# WS2812B_Bar.net
KiCad netlist of a schematic drawn in Altium Designer
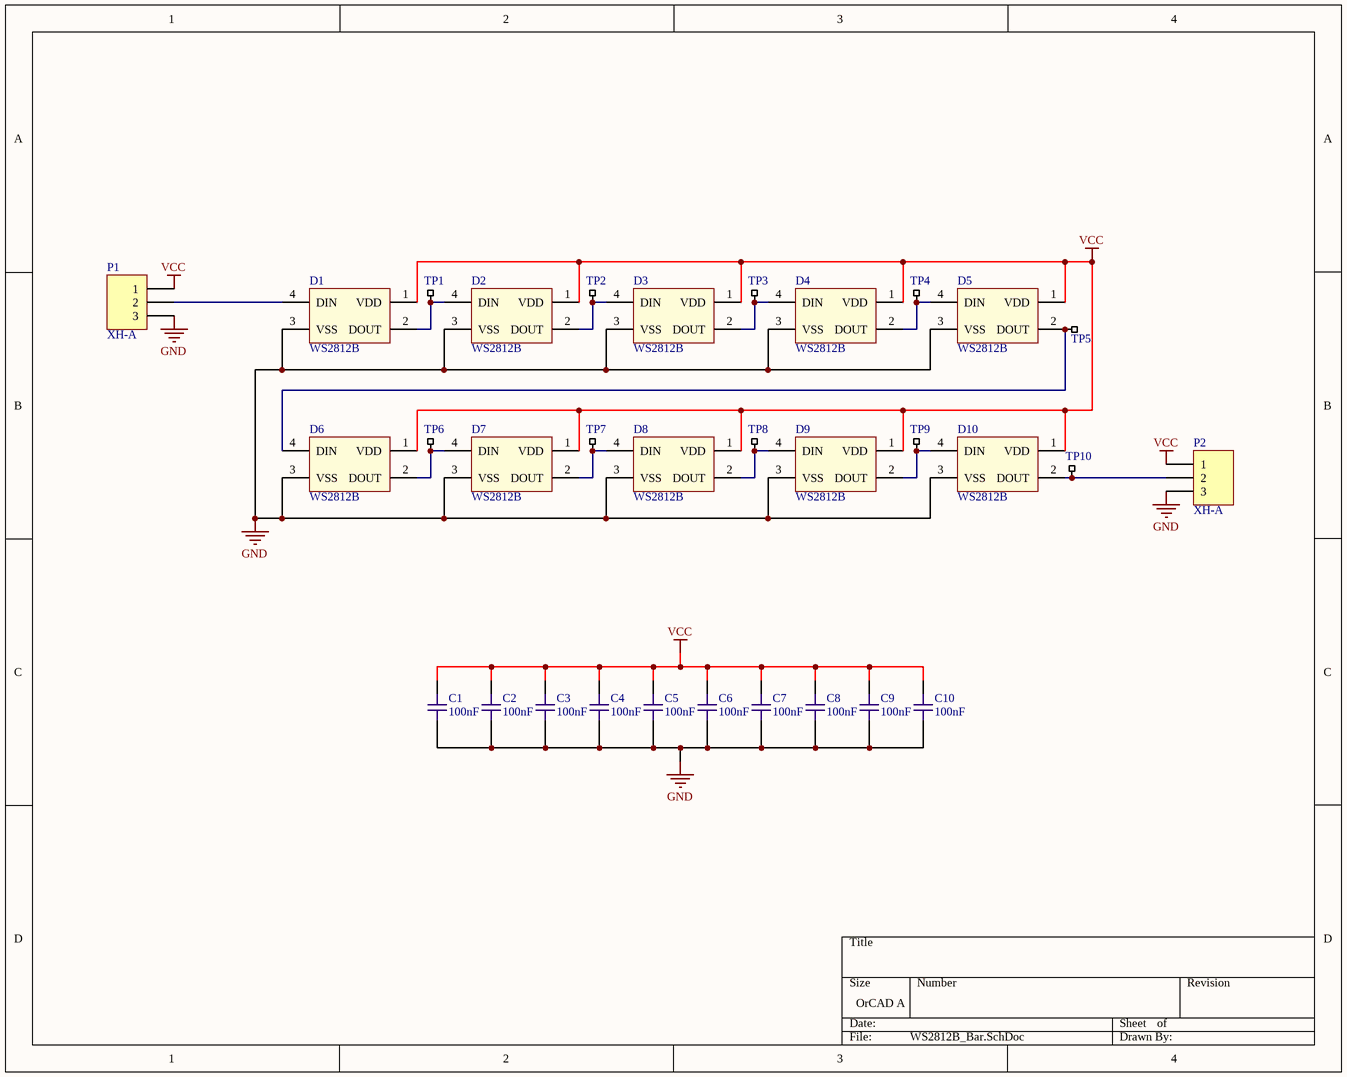
[diagram p0: WS2812B_Bar.SchDoc]

(export (version "E")
  (design (tool "Eeschema 10.0.6"))
  (components
    (comp (ref "C1")
      (value "100nF")
      (footprint "C0603-IPC")
      (description "Chip Capacitor, 0603, 100nF, 25V, X7R")
      (fields (field (name "Comment") "C0603 100nF 25V X7R"))
      (libsource (lib "Capacitors") (part "C0603 100nF 25V X7R"))
    )
    (comp (ref "C2")
      (value "100nF")
      (footprint "C0603-IPC")
      (description "Chip Capacitor, 0603, 100nF, 25V, X7R")
      (fields (field (name "Comment") "C0603 100nF 25V X7R"))
      (libsource (lib "Capacitors") (part "C0603 100nF 25V X7R"))
    )
    (comp (ref "C3")
      (value "100nF")
      (footprint "C0603-IPC")
      (description "Chip Capacitor, 0603, 100nF, 25V, X7R")
      (fields (field (name "Comment") "C0603 100nF 25V X7R"))
      (libsource (lib "Capacitors") (part "C0603 100nF 25V X7R"))
    )
    (comp (ref "C4")
      (value "100nF")
      (footprint "C0603-IPC")
      (description "Chip Capacitor, 0603, 100nF, 25V, X7R")
      (fields (field (name "Comment") "C0603 100nF 25V X7R"))
      (libsource (lib "Capacitors") (part "C0603 100nF 25V X7R"))
    )
    (comp (ref "C5")
      (value "100nF")
      (footprint "C0603-IPC")
      (description "Chip Capacitor, 0603, 100nF, 25V, X7R")
      (fields (field (name "Comment") "C0603 100nF 25V X7R"))
      (libsource (lib "Capacitors") (part "C0603 100nF 25V X7R"))
    )
    (comp (ref "C6")
      (value "100nF")
      (footprint "C0603-IPC")
      (description "Chip Capacitor, 0603, 100nF, 25V, X7R")
      (fields (field (name "Comment") "C0603 100nF 25V X7R"))
      (libsource (lib "Capacitors") (part "C0603 100nF 25V X7R"))
    )
    (comp (ref "C7")
      (value "100nF")
      (footprint "C0603-IPC")
      (description "Chip Capacitor, 0603, 100nF, 25V, X7R")
      (fields (field (name "Comment") "C0603 100nF 25V X7R"))
      (libsource (lib "Capacitors") (part "C0603 100nF 25V X7R"))
    )
    (comp (ref "C8")
      (value "100nF")
      (footprint "C0603-IPC")
      (description "Chip Capacitor, 0603, 100nF, 25V, X7R")
      (fields (field (name "Comment") "C0603 100nF 25V X7R"))
      (libsource (lib "Capacitors") (part "C0603 100nF 25V X7R"))
    )
    (comp (ref "C9")
      (value "100nF")
      (footprint "C0603-IPC")
      (description "Chip Capacitor, 0603, 100nF, 25V, X7R")
      (fields (field (name "Comment") "C0603 100nF 25V X7R"))
      (libsource (lib "Capacitors") (part "C0603 100nF 25V X7R"))
    )
    (comp (ref "C10")
      (value "100nF")
      (footprint "C0603-IPC")
      (description "Chip Capacitor, 0603, 100nF, 25V, X7R")
      (fields (field (name "Comment") "C0603 100nF 25V X7R"))
      (libsource (lib "Capacitors") (part "C0603 100nF 25V X7R"))
    )
    (comp (ref "D1")
      (value "WS2812B")
      (footprint "WS2812B")
      (description "Addressable Lighting - Discrete Serial Red, Green, Blue (RGB) 5.00mm L x 5.00mm WS2812B")
      (libsource (lib "Diodes") (part "WS2812B"))
    )
    (comp (ref "D2")
      (value "WS2812B")
      (footprint "WS2812B")
      (description "Addressable Lighting - Discrete Serial Red, Green, Blue (RGB) 5.00mm L x 5.00mm WS2812B")
      (libsource (lib "Diodes") (part "WS2812B"))
    )
    (comp (ref "D3")
      (value "WS2812B")
      (footprint "WS2812B")
      (description "Addressable Lighting - Discrete Serial Red, Green, Blue (RGB) 5.00mm L x 5.00mm WS2812B")
      (libsource (lib "Diodes") (part "WS2812B"))
    )
    (comp (ref "D4")
      (value "WS2812B")
      (footprint "WS2812B")
      (description "Addressable Lighting - Discrete Serial Red, Green, Blue (RGB) 5.00mm L x 5.00mm WS2812B")
      (libsource (lib "Diodes") (part "WS2812B"))
    )
    (comp (ref "D5")
      (value "WS2812B")
      (footprint "WS2812B")
      (description "Addressable Lighting - Discrete Serial Red, Green, Blue (RGB) 5.00mm L x 5.00mm WS2812B")
      (libsource (lib "Diodes") (part "WS2812B"))
    )
    (comp (ref "D6")
      (value "WS2812B")
      (footprint "WS2812B")
      (description "Addressable Lighting - Discrete Serial Red, Green, Blue (RGB) 5.00mm L x 5.00mm WS2812B")
      (libsource (lib "Diodes") (part "WS2812B"))
    )
    (comp (ref "D7")
      (value "WS2812B")
      (footprint "WS2812B")
      (description "Addressable Lighting - Discrete Serial Red, Green, Blue (RGB) 5.00mm L x 5.00mm WS2812B")
      (libsource (lib "Diodes") (part "WS2812B"))
    )
    (comp (ref "D8")
      (value "WS2812B")
      (footprint "WS2812B")
      (description "Addressable Lighting - Discrete Serial Red, Green, Blue (RGB) 5.00mm L x 5.00mm WS2812B")
      (libsource (lib "Diodes") (part "WS2812B"))
    )
    (comp (ref "D9")
      (value "WS2812B")
      (footprint "WS2812B")
      (description "Addressable Lighting - Discrete Serial Red, Green, Blue (RGB) 5.00mm L x 5.00mm WS2812B")
      (libsource (lib "Diodes") (part "WS2812B"))
    )
    (comp (ref "D10")
      (value "WS2812B")
      (footprint "WS2812B")
      (description "Addressable Lighting - Discrete Serial Red, Green, Blue (RGB) 5.00mm L x 5.00mm WS2812B")
      (libsource (lib "Diodes") (part "WS2812B"))
    )
    (comp (ref "P1")
      (value "XH-A")
      (footprint "XH Header 1x3 SMD 2.5MM HORIZONTAL")
      (description "XH Header Male Pin 0.098\"(2.50mm) 3 Wire To Board / Wire To Wire Connector")
      (fields (field (name "PUBLISHER") "Altium Limited"))
      (libsource (lib "") (part "JST XH 1x3_1"))
    )
    (comp (ref "P2")
      (value "XH-A")
      (footprint "XH Header 1x3 SMD 2.5MM HORIZONTAL")
      (description "XH Header Male Pin 0.098\"(2.50mm) 3 Wire To Board / Wire To Wire Connector")
      (fields (field (name "PUBLISHER") "Altium Limited"))
      (libsource (lib "Connectors") (part "JST XH 1x3"))
    )
    (comp (ref "TP1")
      (value "Testpoint_SMT")
      (footprint "TESTPOINT_SMT")
      (description "SMT Test Point")
      (libsource (lib "Virtual Parts") (part "Testpoint_SMT"))
    )
    (comp (ref "TP2")
      (value "Testpoint_SMT")
      (footprint "TESTPOINT_SMT")
      (description "SMT Test Point")
      (libsource (lib "Virtual Parts") (part "Testpoint_SMT"))
    )
    (comp (ref "TP3")
      (value "Testpoint_SMT")
      (footprint "TESTPOINT_SMT")
      (description "SMT Test Point")
      (libsource (lib "Virtual Parts") (part "Testpoint_SMT"))
    )
    (comp (ref "TP4")
      (value "Testpoint_SMT")
      (footprint "TESTPOINT_SMT")
      (description "SMT Test Point")
      (libsource (lib "Virtual Parts") (part "Testpoint_SMT"))
    )
    (comp (ref "TP5")
      (value "Testpoint_SMT")
      (footprint "TESTPOINT_SMT")
      (description "SMT Test Point")
      (libsource (lib "Virtual Parts") (part "Testpoint_SMT"))
    )
    (comp (ref "TP6")
      (value "Testpoint_SMT")
      (footprint "TESTPOINT_SMT")
      (description "SMT Test Point")
      (libsource (lib "Virtual Parts") (part "Testpoint_SMT"))
    )
    (comp (ref "TP7")
      (value "Testpoint_SMT")
      (footprint "TESTPOINT_SMT")
      (description "SMT Test Point")
      (libsource (lib "Virtual Parts") (part "Testpoint_SMT"))
    )
    (comp (ref "TP8")
      (value "Testpoint_SMT")
      (footprint "TESTPOINT_SMT")
      (description "SMT Test Point")
      (libsource (lib "Virtual Parts") (part "Testpoint_SMT"))
    )
    (comp (ref "TP9")
      (value "Testpoint_SMT")
      (footprint "TESTPOINT_SMT")
      (description "SMT Test Point")
      (libsource (lib "Virtual Parts") (part "Testpoint_SMT"))
    )
    (comp (ref "TP10")
      (value "Testpoint_SMT")
      (footprint "TESTPOINT_SMT")
      (description "SMT Test Point")
      (libsource (lib "Virtual Parts") (part "Testpoint_SMT"))
    )
  )
  (nets
    (net (code "1") (name "GND") (class "Default")
      (node (ref "C1") (pin "1") (pintype "passive"))
      (node (ref "C10") (pin "1") (pintype "passive"))
      (node (ref "C2") (pin "1") (pintype "passive"))
      (node (ref "C3") (pin "1") (pintype "passive"))
      (node (ref "C4") (pin "1") (pintype "passive"))
      (node (ref "C5") (pin "1") (pintype "passive"))
      (node (ref "C6") (pin "1") (pintype "passive"))
      (node (ref "C7") (pin "1") (pintype "passive"))
      (node (ref "C8") (pin "1") (pintype "passive"))
      (node (ref "C9") (pin "1") (pintype "passive"))
      (node (ref "D1") (pin "3") (pinfunction "VSS_3") (pintype "passive"))
      (node (ref "D10") (pin "3") (pinfunction "VSS_3") (pintype "passive"))
      (node (ref "D2") (pin "3") (pinfunction "VSS_3") (pintype "passive"))
      (node (ref "D3") (pin "3") (pinfunction "VSS_3") (pintype "passive"))
      (node (ref "D4") (pin "3") (pinfunction "VSS_3") (pintype "passive"))
      (node (ref "D5") (pin "3") (pinfunction "VSS_3") (pintype "passive"))
      (node (ref "D6") (pin "3") (pinfunction "VSS_3") (pintype "passive"))
      (node (ref "D7") (pin "3") (pinfunction "VSS_3") (pintype "passive"))
      (node (ref "D8") (pin "3") (pinfunction "VSS_3") (pintype "passive"))
      (node (ref "D9") (pin "3") (pinfunction "VSS_3") (pintype "passive"))
      (node (ref "P1") (pin "3") (pinfunction "3_3") (pintype "passive"))
      (node (ref "P2") (pin "3") (pinfunction "3_3") (pintype "passive"))
    )
    (net (code "2") (name "Net-(D1-DIN)") (class "Default")
      (node (ref "D1") (pin "4") (pinfunction "DIN_4") (pintype "passive"))
      (node (ref "P1") (pin "2") (pinfunction "2_2") (pintype "passive"))
    )
    (net (code "3") (name "Net-(D1-DOUT)") (class "Default")
      (node (ref "D1") (pin "2") (pinfunction "DOUT_2") (pintype "passive"))
      (node (ref "D2") (pin "4") (pinfunction "DIN_4") (pintype "passive"))
      (node (ref "TP1") (pin "1") (pinfunction "1_1") (pintype "passive"))
    )
    (net (code "4") (name "Net-(D2-DOUT)") (class "Default")
      (node (ref "D2") (pin "2") (pinfunction "DOUT_2") (pintype "passive"))
      (node (ref "D3") (pin "4") (pinfunction "DIN_4") (pintype "passive"))
      (node (ref "TP2") (pin "1") (pinfunction "1_1") (pintype "passive"))
    )
    (net (code "5") (name "Net-(D3-DOUT)") (class "Default")
      (node (ref "D3") (pin "2") (pinfunction "DOUT_2") (pintype "passive"))
      (node (ref "D4") (pin "4") (pinfunction "DIN_4") (pintype "passive"))
      (node (ref "TP3") (pin "1") (pinfunction "1_1") (pintype "passive"))
    )
    (net (code "6") (name "Net-(D4-DOUT)") (class "Default")
      (node (ref "D4") (pin "2") (pinfunction "DOUT_2") (pintype "passive"))
      (node (ref "D5") (pin "4") (pinfunction "DIN_4") (pintype "passive"))
      (node (ref "TP4") (pin "1") (pinfunction "1_1") (pintype "passive"))
    )
    (net (code "7") (name "Net-(D5-DOUT)") (class "Default")
      (node (ref "D5") (pin "2") (pinfunction "DOUT_2") (pintype "passive"))
      (node (ref "D6") (pin "4") (pinfunction "DIN_4") (pintype "passive"))
      (node (ref "TP5") (pin "1") (pinfunction "1_1") (pintype "passive"))
    )
    (net (code "8") (name "Net-(D6-DOUT)") (class "Default")
      (node (ref "D6") (pin "2") (pinfunction "DOUT_2") (pintype "passive"))
      (node (ref "D7") (pin "4") (pinfunction "DIN_4") (pintype "passive"))
      (node (ref "TP6") (pin "1") (pinfunction "1_1") (pintype "passive"))
    )
    (net (code "9") (name "Net-(D7-DOUT)") (class "Default")
      (node (ref "D7") (pin "2") (pinfunction "DOUT_2") (pintype "passive"))
      (node (ref "D8") (pin "4") (pinfunction "DIN_4") (pintype "passive"))
      (node (ref "TP7") (pin "1") (pinfunction "1_1") (pintype "passive"))
    )
    (net (code "10") (name "Net-(D8-DOUT)") (class "Default")
      (node (ref "D8") (pin "2") (pinfunction "DOUT_2") (pintype "passive"))
      (node (ref "D9") (pin "4") (pinfunction "DIN_4") (pintype "passive"))
      (node (ref "TP8") (pin "1") (pinfunction "1_1") (pintype "passive"))
    )
    (net (code "11") (name "Net-(D10-DIN)") (class "Default")
      (node (ref "D10") (pin "4") (pinfunction "DIN_4") (pintype "passive"))
      (node (ref "D9") (pin "2") (pinfunction "DOUT_2") (pintype "passive"))
      (node (ref "TP9") (pin "1") (pinfunction "1_1") (pintype "passive"))
    )
    (net (code "12") (name "Net-(D10-DOUT)") (class "Default")
      (node (ref "D10") (pin "2") (pinfunction "DOUT_2") (pintype "passive"))
      (node (ref "P2") (pin "2") (pinfunction "2_2") (pintype "passive"))
      (node (ref "TP10") (pin "1") (pinfunction "1_1") (pintype "passive"))
    )
    (net (code "13") (name "VCC") (class "Default")
      (node (ref "C1") (pin "2") (pintype "passive"))
      (node (ref "C10") (pin "2") (pintype "passive"))
      (node (ref "C2") (pin "2") (pintype "passive"))
      (node (ref "C3") (pin "2") (pintype "passive"))
      (node (ref "C4") (pin "2") (pintype "passive"))
      (node (ref "C5") (pin "2") (pintype "passive"))
      (node (ref "C6") (pin "2") (pintype "passive"))
      (node (ref "C7") (pin "2") (pintype "passive"))
      (node (ref "C8") (pin "2") (pintype "passive"))
      (node (ref "C9") (pin "2") (pintype "passive"))
      (node (ref "D1") (pin "1") (pinfunction "VDD_1") (pintype "passive"))
      (node (ref "D10") (pin "1") (pinfunction "VDD_1") (pintype "passive"))
      (node (ref "D2") (pin "1") (pinfunction "VDD_1") (pintype "passive"))
      (node (ref "D3") (pin "1") (pinfunction "VDD_1") (pintype "passive"))
      (node (ref "D4") (pin "1") (pinfunction "VDD_1") (pintype "passive"))
      (node (ref "D5") (pin "1") (pinfunction "VDD_1") (pintype "passive"))
      (node (ref "D6") (pin "1") (pinfunction "VDD_1") (pintype "passive"))
      (node (ref "D7") (pin "1") (pinfunction "VDD_1") (pintype "passive"))
      (node (ref "D8") (pin "1") (pinfunction "VDD_1") (pintype "passive"))
      (node (ref "D9") (pin "1") (pinfunction "VDD_1") (pintype "passive"))
      (node (ref "P1") (pin "1") (pinfunction "1_1") (pintype "passive"))
      (node (ref "P2") (pin "1") (pinfunction "1_1") (pintype "passive"))
    )
  )
)
